# Atrix_breakout.net
KiCad netlist of a schematic drawn in EAGLE
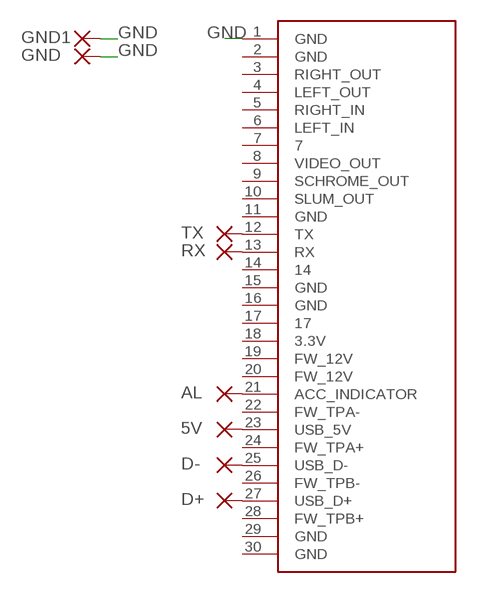
[diagram p0: schematic, sheet 1]

(export (version "E")
  (design (tool "Eeschema 10.0.6"))
  (components
    (comp (ref "5V")
      (value "1,6/0,8")
      (footprint "eagle-import:1,6_0,8")
      (libsource (lib "eagle-import") (part "1,6/0,8"))
    )
    (comp (ref "AL")
      (value "1,6/0,8")
      (footprint "eagle-import:1,6_0,8")
      (libsource (lib "eagle-import") (part "1,6/0,8"))
    )
    (comp (ref "D+")
      (value "1,6/0,8")
      (footprint "eagle-import:1,6_0,8")
      (libsource (lib "eagle-import") (part "1,6/0,8"))
    )
    (comp (ref "D-")
      (value "1,6/0,8")
      (footprint "eagle-import:1,6_0,8")
      (libsource (lib "eagle-import") (part "1,6/0,8"))
    )
    (comp (ref "GND")
      (value "1,6/0,8")
      (footprint "eagle-import:1,6_0,8")
      (libsource (lib "eagle-import") (part "1,6/0,8"))
    )
    (comp (ref "GND1")
      (value "1,6/0,8")
      (footprint "eagle-import:1,6_0,8")
      (libsource (lib "eagle-import") (part "1,6/0,8"))
    )
    (comp (ref "RX")
      (value "1,6/0,8")
      (footprint "eagle-import:1,6_0,8")
      (libsource (lib "eagle-import") (part "1,6/0,8"))
    )
    (comp (ref "TX")
      (value "1,6/0,8")
      (footprint "eagle-import:1,6_0,8")
      (libsource (lib "eagle-import") (part "1,6/0,8"))
    )
    (comp (ref "U$1")
      (value "IPOD_CONNECTOR_MALE")
      (footprint "eagle-import:IPOD_MALE_CONNECTOR")
      (libsource (lib "eagle-import") (part "IPOD_CONNECTOR_MALE"))
    )
  )
  (nets
    (net (code "1") (name "/GND") (class "Default")
      (node (ref "GND") (pin "1") (pinfunction "P_1") (pintype "passive"))
      (node (ref "GND1") (pin "1") (pinfunction "P_1") (pintype "passive"))
      (node (ref "U$1") (pin "1") (pinfunction "GND_1") (pintype "bidirectional"))
    )
    (net (code "2") (name "Net-(5V-P)") (class "Default")
      (node (ref "5V") (pin "1") (pinfunction "P_1") (pintype "passive"))
      (node (ref "U$1") (pin "23") (pinfunction "USB_5V_23") (pintype "bidirectional"))
    )
    (net (code "3") (name "Net-(AL-P)") (class "Default")
      (node (ref "AL") (pin "1") (pinfunction "P_1") (pintype "passive"))
      (node (ref "U$1") (pin "21") (pinfunction "ACC_INDICATOR_21") (pintype "bidirectional"))
    )
    (net (code "4") (name "Net-(D+-P)") (class "Default")
      (node (ref "D+") (pin "1") (pinfunction "P_1") (pintype "passive"))
      (node (ref "U$1") (pin "27") (pinfunction "USB_D+_27") (pintype "bidirectional"))
    )
    (net (code "5") (name "Net-(D--P)") (class "Default")
      (node (ref "D-") (pin "1") (pinfunction "P_1") (pintype "passive"))
      (node (ref "U$1") (pin "25") (pinfunction "USB_D-_25") (pintype "bidirectional"))
    )
    (net (code "6") (name "Net-(RX-P)") (class "Default")
      (node (ref "RX") (pin "1") (pinfunction "P_1") (pintype "passive"))
      (node (ref "U$1") (pin "13") (pinfunction "RX_13") (pintype "bidirectional"))
    )
    (net (code "7") (name "Net-(TX-P)") (class "Default")
      (node (ref "TX") (pin "1") (pinfunction "P_1") (pintype "passive"))
      (node (ref "U$1") (pin "12") (pinfunction "TX_12") (pintype "bidirectional"))
    )
    (net (code "8") (name "unconnected-(U$1-3.3V-Pad18)") (class "Default")
      (node (ref "U$1") (pin "18") (pinfunction "3.3V_18") (pintype "bidirectional"))
    )
    (net (code "9") (name "unconnected-(U$1-FW_12V-Pad19)") (class "Default")
      (node (ref "U$1") (pin "19") (pinfunction "FW_12V_19") (pintype "bidirectional"))
    )
    (net (code "10") (name "unconnected-(U$1-FW_12V-Pad20)") (class "Default")
      (node (ref "U$1") (pin "20") (pinfunction "FW_12V_20") (pintype "bidirectional"))
    )
    (net (code "11") (name "unconnected-(U$1-FW_TPA+-Pad24)") (class "Default")
      (node (ref "U$1") (pin "24") (pinfunction "FW_TPA+_24") (pintype "bidirectional"))
    )
    (net (code "12") (name "unconnected-(U$1-FW_TPA--Pad22)") (class "Default")
      (node (ref "U$1") (pin "22") (pinfunction "FW_TPA-_22") (pintype "bidirectional"))
    )
    (net (code "13") (name "unconnected-(U$1-FW_TPB+-Pad28)") (class "Default")
      (node (ref "U$1") (pin "28") (pinfunction "FW_TPB+_28") (pintype "bidirectional"))
    )
    (net (code "14") (name "unconnected-(U$1-FW_TPB--Pad26)") (class "Default")
      (node (ref "U$1") (pin "26") (pinfunction "FW_TPB-_26") (pintype "bidirectional"))
    )
    (net (code "15") (name "unconnected-(U$1-GND-Pad2)") (class "Default")
      (node (ref "U$1") (pin "2") (pinfunction "GND_2") (pintype "bidirectional"))
    )
    (net (code "16") (name "unconnected-(U$1-GND-Pad11)") (class "Default")
      (node (ref "U$1") (pin "11") (pinfunction "GND_11") (pintype "bidirectional"))
    )
    (net (code "17") (name "unconnected-(U$1-GND-Pad15)") (class "Default")
      (node (ref "U$1") (pin "15") (pinfunction "GND_15") (pintype "bidirectional"))
    )
    (net (code "18") (name "unconnected-(U$1-GND-Pad16)") (class "Default")
      (node (ref "U$1") (pin "16") (pinfunction "GND_16") (pintype "bidirectional"))
    )
    (net (code "19") (name "unconnected-(U$1-GND-Pad29)") (class "Default")
      (node (ref "U$1") (pin "29") (pinfunction "GND_29") (pintype "bidirectional"))
    )
    (net (code "20") (name "unconnected-(U$1-GND-Pad30)") (class "Default")
      (node (ref "U$1") (pin "30") (pinfunction "GND_30") (pintype "bidirectional"))
    )
    (net (code "21") (name "unconnected-(U$1-LEFT_IN-Pad6)") (class "Default")
      (node (ref "U$1") (pin "6") (pinfunction "LEFT_IN_6") (pintype "bidirectional"))
    )
    (net (code "22") (name "unconnected-(U$1-LEFT_OUT-Pad4)") (class "Default")
      (node (ref "U$1") (pin "4") (pinfunction "LEFT_OUT_4") (pintype "bidirectional"))
    )
    (net (code "23") (name "unconnected-(U$1-Pad7)") (class "Default")
      (node (ref "U$1") (pin "7") (pinfunction "7_7") (pintype "bidirectional"))
    )
    (net (code "24") (name "unconnected-(U$1-Pad14)") (class "Default")
      (node (ref "U$1") (pin "14") (pinfunction "14_14") (pintype "bidirectional"))
    )
    (net (code "25") (name "unconnected-(U$1-Pad17)") (class "Default")
      (node (ref "U$1") (pin "17") (pinfunction "17_17") (pintype "bidirectional"))
    )
    (net (code "26") (name "unconnected-(U$1-RIGHT_IN-Pad5)") (class "Default")
      (node (ref "U$1") (pin "5") (pinfunction "RIGHT_IN_5") (pintype "bidirectional"))
    )
    (net (code "27") (name "unconnected-(U$1-RIGHT_OUT-Pad3)") (class "Default")
      (node (ref "U$1") (pin "3") (pinfunction "RIGHT_OUT_3") (pintype "bidirectional"))
    )
    (net (code "28") (name "unconnected-(U$1-SCHROME_OUT-Pad9)") (class "Default")
      (node (ref "U$1") (pin "9") (pinfunction "SCHROME_OUT_9") (pintype "bidirectional"))
    )
    (net (code "29") (name "unconnected-(U$1-SLUM_OUT-Pad10)") (class "Default")
      (node (ref "U$1") (pin "10") (pinfunction "SLUM_OUT_10") (pintype "bidirectional"))
    )
    (net (code "30") (name "unconnected-(U$1-VIDEO_OUT-Pad8)") (class "Default")
      (node (ref "U$1") (pin "8") (pinfunction "VIDEO_OUT_8") (pintype "bidirectional"))
    )
  )
)
